# Wireless.net
KiCad netlist of a schematic drawn in Altium Designer
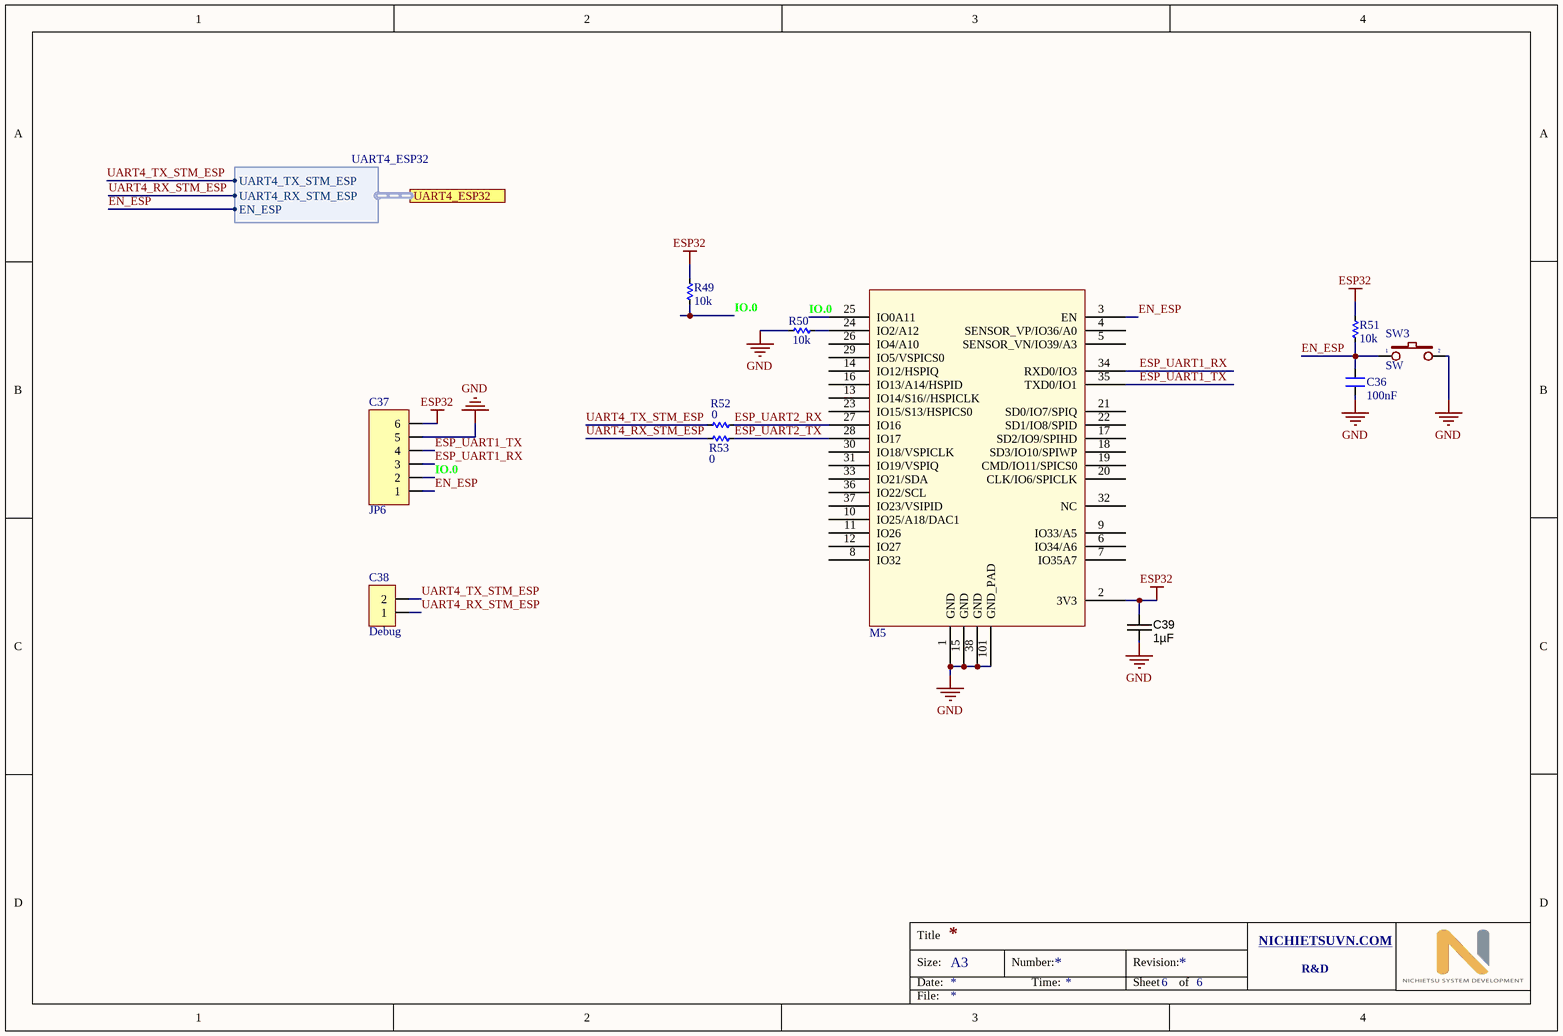
[diagram p0: Wireless.SchDoc]

(export (version "E")
  (design (tool "Eeschema 10.0.6"))
  (components
    (comp (ref "C36") (value "100nF") (footprint "CN-SMD-0603") (libsource (lib "thu vien 3d") (part "CN")))
    (comp (ref "C37")
      (value "JP6")
      (footprint "JP6-D1T")
      (description "WR-PHD 2.54 mm Angled Socket Header")
      (fields
        (field (name "MANUFACTURER") "Würth Elektronik eiSos GmbH")
        (field (name "PARTNO") "613006143121")
        (field (name "CREATED BY") "Karrer Zheng")
      )
      (libsource (lib "thu vien 3d") (part "JP6"))
    )
    (comp (ref "C38")
      (value "Debug")
      (footprint "JP2-CLOSED")
      (description "WR-PHD 2.54 mm Angled Socket Header")
      (fields
        (field (name "MANUFACTURER") "Würth Elektronik eiSos GmbH")
        (field (name "PARTNO") "613002143121")
        (field (name "CREATED BY") "Karrer Zheng")
      )
      (libsource (lib "thu vien 3d") (part "JP2"))
    )
    (comp (ref "C39")
      (value "1µF")
      (footprint "CAPC1608X90N")
      (description "1µF ±10% 16V Ceramic Capacitor X7R 0603 (1608 Metric)")
      (fields (field (name "TOLERANCE") "±10%"))
      (libsource (lib "All Library") (part "CAPC_1uF_0603_X7R_35V_10%"))
    )
    (comp (ref "M5")
      (value "ESP32S_Module")
      (footprint "ESP32S")
      (description "Esp-32S")
      (libsource (lib "Nichietsuvn") (part "ESP32S_Module"))
    )
    (comp (ref "R49")
      (value "10k")
      (footprint "RES-SMD-0603")
      (description "Resistor")
      (fields
        (field (name "MANUFACTURER") "Generic Components")
        (field (name "PUBLISHER") "Altium Hobart Technology Centre")
      )
      (libsource (lib "thu vien 3d") (part "Res-SMD"))
    )
    (comp (ref "R50")
      (value "10k")
      (footprint "RES-SMD-0603")
      (description "Resistor")
      (fields
        (field (name "MANUFACTURER") "Generic Components")
        (field (name "PUBLISHER") "Altium Hobart Technology Centre")
      )
      (libsource (lib "thu vien 3d") (part "Res-SMD"))
    )
    (comp (ref "R51")
      (value "10k")
      (footprint "RES-SMD-0603")
      (description "Resistor")
      (fields
        (field (name "MANUFACTURER") "Generic Components")
        (field (name "PUBLISHER") "Altium Hobart Technology Centre")
      )
      (libsource (lib "thu vien 3d") (part "Res-SMD"))
    )
    (comp (ref "R52")
      (value "0")
      (footprint "RES-SMD-0603")
      (description "Resistor")
      (fields
        (field (name "MANUFACTURER") "Generic Components")
        (field (name "PUBLISHER") "Altium Hobart Technology Centre")
      )
      (libsource (lib "thu vien 3d") (part "Res-SMD"))
    )
    (comp (ref "R53")
      (value "0")
      (footprint "RES-SMD-0603")
      (description "Resistor")
      (fields
        (field (name "MANUFACTURER") "Generic Components")
        (field (name "PUBLISHER") "Altium Hobart Technology Centre")
      )
      (libsource (lib "thu vien 3d") (part "Res-SMD"))
    )
    (comp (ref "SW3")
      (value "SW")
      (footprint "SW1-SMD")
      (description "Switch button 2 pin")
      (libsource (lib "thu vien 3d") (part "SW2"))
    )
  )
  (nets
    (net (code "2") (name "/EN_ESP") (class "Default")
      (node (ref "C36") (pin "1") (pinfunction "1_1") (pintype "passive"))
      (node (ref "C37") (pin "1") (pinfunction "1_1") (pintype "passive"))
      (node (ref "M5") (pin "3") (pinfunction "EN_3") (pintype "power_in"))
      (node (ref "R51") (pin "2") (pinfunction "2_2") (pintype "passive"))
      (node (ref "SW3") (pin "1") (pinfunction "1_1") (pintype "passive"))
    )
    (net (code "3") (name "/ESP_UART1_RX") (class "Default")
      (node (ref "C37") (pin "3") (pinfunction "3_3") (pintype "passive"))
      (node (ref "M5") (pin "34") (pinfunction "RXD0/IO3_34") (pintype "passive"))
    )
    (net (code "4") (name "/ESP_UART1_TX") (class "Default")
      (node (ref "C37") (pin "4") (pinfunction "4_4") (pintype "passive"))
      (node (ref "M5") (pin "35") (pinfunction "TXD0/IO1_35") (pintype "passive"))
    )
    (net (code "5") (name "/ESP_UART2_RX") (class "Default")
      (node (ref "M5") (pin "27") (pinfunction "IO16_27") (pintype "passive"))
      (node (ref "R52") (pin "1") (pinfunction "1_1") (pintype "passive"))
    )
    (net (code "6") (name "/ESP_UART2_TX") (class "Default")
      (node (ref "M5") (pin "28") (pinfunction "IO17_28") (pintype "passive"))
      (node (ref "R53") (pin "1") (pinfunction "1_1") (pintype "passive"))
    )
    (net (code "7") (name "/IO.0") (class "Default")
      (node (ref "C37") (pin "2") (pinfunction "2_2") (pintype "passive"))
      (node (ref "M5") (pin "25") (pinfunction "IO0A11_25") (pintype "passive"))
      (node (ref "R49") (pin "2") (pinfunction "2_2") (pintype "passive"))
    )
    (net (code "8") (name "/UART4_RX_STM_ESP") (class "Default")
      (node (ref "C38") (pin "1") (pinfunction "1_1") (pintype "passive"))
      (node (ref "R53") (pin "2") (pinfunction "2_2") (pintype "passive"))
    )
    (net (code "9") (name "/UART4_TX_STM_ESP") (class "Default")
      (node (ref "C38") (pin "2") (pinfunction "2_2") (pintype "passive"))
      (node (ref "R52") (pin "2") (pinfunction "2_2") (pintype "passive"))
    )
    (net (code "11") (name "ESP32") (class "Default")
      (node (ref "C37") (pin "6") (pinfunction "6_6") (pintype "passive"))
      (node (ref "C39") (pin "1") (pintype "passive"))
      (node (ref "M5") (pin "2") (pinfunction "3V3_2") (pintype "power_in"))
      (node (ref "R49") (pin "1") (pinfunction "1_1") (pintype "passive"))
      (node (ref "R51") (pin "1") (pinfunction "1_1") (pintype "passive"))
    )
    (net (code "12") (name "GND") (class "Default")
      (node (ref "C36") (pin "2") (pinfunction "2_2") (pintype "passive"))
      (node (ref "C37") (pin "5") (pinfunction "5_5") (pintype "passive"))
      (node (ref "C39") (pin "2") (pintype "passive"))
      (node (ref "M5") (pin "1") (pinfunction "GND_1") (pintype "power_in"))
      (node (ref "M5") (pin "101") (pinfunction "GND_PAD_101") (pintype "power_in"))
      (node (ref "M5") (pin "15") (pinfunction "GND_15") (pintype "power_in"))
      (node (ref "M5") (pin "38") (pinfunction "GND_38") (pintype "power_in"))
      (node (ref "R50") (pin "1") (pinfunction "1_1") (pintype "passive"))
      (node (ref "SW3") (pin "2") (pinfunction "2_2") (pintype "passive"))
    )
    (net (code "13") (name "Net-(M5-IO2{slash}A12)") (class "Default")
      (node (ref "M5") (pin "24") (pinfunction "IO2/A12_24") (pintype "passive"))
      (node (ref "R50") (pin "2") (pinfunction "2_2") (pintype "passive"))
    )
    (net (code "14") (name "unconnected-(M5-CLK{slash}IO6{slash}SPICLK-Pad20)") (class "Default")
      (node (ref "M5") (pin "20") (pinfunction "CLK/IO6/SPICLK_20") (pintype "passive"))
    )
    (net (code "15") (name "unconnected-(M5-CMD{slash}IO11{slash}SPICS0-Pad19)") (class "Default")
      (node (ref "M5") (pin "19") (pinfunction "CMD/IO11/SPICS0_19") (pintype "passive"))
    )
    (net (code "16") (name "unconnected-(M5-IO4{slash}A10-Pad26)") (class "Default")
      (node (ref "M5") (pin "26") (pinfunction "IO4/A10_26") (pintype "passive"))
    )
    (net (code "17") (name "unconnected-(M5-IO5{slash}VSPICS0-Pad29)") (class "Default")
      (node (ref "M5") (pin "29") (pinfunction "IO5/VSPICS0_29") (pintype "passive"))
    )
    (net (code "18") (name "unconnected-(M5-IO12{slash}HSPIQ-Pad14)") (class "Default")
      (node (ref "M5") (pin "14") (pinfunction "IO12/HSPIQ_14") (pintype "passive"))
    )
    (net (code "19") (name "unconnected-(M5-IO13{slash}A14{slash}HSPID-Pad16)") (class "Default")
      (node (ref "M5") (pin "16") (pinfunction "IO13/A14/HSPID_16") (pintype "passive"))
    )
    (net (code "20") (name "unconnected-(M5-IO14{slash}S16{slash}{slash}HSPICLK-Pad13)") (class "Default")
      (node (ref "M5") (pin "13") (pinfunction "IO14/S16//HSPICLK_13") (pintype "passive"))
    )
    (net (code "21") (name "unconnected-(M5-IO15{slash}S13{slash}HSPICS0-Pad23)") (class "Default")
      (node (ref "M5") (pin "23") (pinfunction "IO15/S13/HSPICS0_23") (pintype "passive"))
    )
    (net (code "22") (name "unconnected-(M5-IO18{slash}VSPICLK-Pad30)") (class "Default")
      (node (ref "M5") (pin "30") (pinfunction "IO18/VSPICLK_30") (pintype "passive"))
    )
    (net (code "23") (name "unconnected-(M5-IO19{slash}VSPIQ-Pad31)") (class "Default")
      (node (ref "M5") (pin "31") (pinfunction "IO19/VSPIQ_31") (pintype "passive"))
    )
    (net (code "24") (name "unconnected-(M5-IO21{slash}SDA-Pad33)") (class "Default")
      (node (ref "M5") (pin "33") (pinfunction "IO21/SDA_33") (pintype "passive"))
    )
    (net (code "25") (name "unconnected-(M5-IO22{slash}SCL-Pad36)") (class "Default")
      (node (ref "M5") (pin "36") (pinfunction "IO22/SCL_36") (pintype "passive"))
    )
    (net (code "26") (name "unconnected-(M5-IO23{slash}VSIPID-Pad37)") (class "Default")
      (node (ref "M5") (pin "37") (pinfunction "IO23/VSIPID_37") (pintype "passive"))
    )
    (net (code "27") (name "unconnected-(M5-IO25{slash}A18{slash}DAC1-Pad10)") (class "Default")
      (node (ref "M5") (pin "10") (pinfunction "IO25/A18/DAC1_10") (pintype "passive"))
    )
    (net (code "28") (name "unconnected-(M5-IO26-Pad11)") (class "Default")
      (node (ref "M5") (pin "11") (pinfunction "IO26_11") (pintype "passive"))
    )
    (net (code "29") (name "unconnected-(M5-IO27-Pad12)") (class "Default")
      (node (ref "M5") (pin "12") (pinfunction "IO27_12") (pintype "passive"))
    )
    (net (code "30") (name "unconnected-(M5-IO32-Pad8)") (class "Default")
      (node (ref "M5") (pin "8") (pinfunction "IO32_8") (pintype "passive"))
    )
    (net (code "31") (name "unconnected-(M5-IO33{slash}A5-Pad9)") (class "Default")
      (node (ref "M5") (pin "9") (pinfunction "IO33/A5_9") (pintype "passive"))
    )
    (net (code "32") (name "unconnected-(M5-IO34{slash}A6-Pad6)") (class "Default")
      (node (ref "M5") (pin "6") (pinfunction "IO34/A6_6") (pintype "passive"))
    )
    (net (code "33") (name "unconnected-(M5-IO35A7-Pad7)") (class "Default")
      (node (ref "M5") (pin "7") (pinfunction "IO35A7_7") (pintype "passive"))
    )
    (net (code "34") (name "unconnected-(M5-NC-Pad32)") (class "Default")
      (node (ref "M5") (pin "32") (pinfunction "NC_32") (pintype "passive"))
    )
    (net (code "35") (name "unconnected-(M5-SD0{slash}IO7{slash}SPIQ-Pad21)") (class "Default")
      (node (ref "M5") (pin "21") (pinfunction "SD0/IO7/SPIQ_21") (pintype "passive"))
    )
    (net (code "36") (name "unconnected-(M5-SD1{slash}IO8{slash}SPID-Pad22)") (class "Default")
      (node (ref "M5") (pin "22") (pinfunction "SD1/IO8/SPID_22") (pintype "passive"))
    )
    (net (code "37") (name "unconnected-(M5-SD2{slash}IO9{slash}SPIHD-Pad17)") (class "Default")
      (node (ref "M5") (pin "17") (pinfunction "SD2/IO9/SPIHD_17") (pintype "passive"))
    )
    (net (code "38") (name "unconnected-(M5-SD3{slash}IO10{slash}SPIWP-Pad18)") (class "Default")
      (node (ref "M5") (pin "18") (pinfunction "SD3/IO10/SPIWP_18") (pintype "passive"))
    )
    (net (code "39") (name "unconnected-(M5-SENSOR_VN{slash}IO39{slash}A3-Pad5)") (class "Default")
      (node (ref "M5") (pin "5") (pinfunction "SENSOR_VN/IO39/A3_5") (pintype "passive"))
    )
    (net (code "40") (name "unconnected-(M5-SENSOR_VP{slash}IO36{slash}A0-Pad4)") (class "Default")
      (node (ref "M5") (pin "4") (pinfunction "SENSOR_VP/IO36/A0_4") (pintype "passive"))
    )
  )
)
